# gwx-control.net
KiCad netlist of a schematic drawn in EAGLE
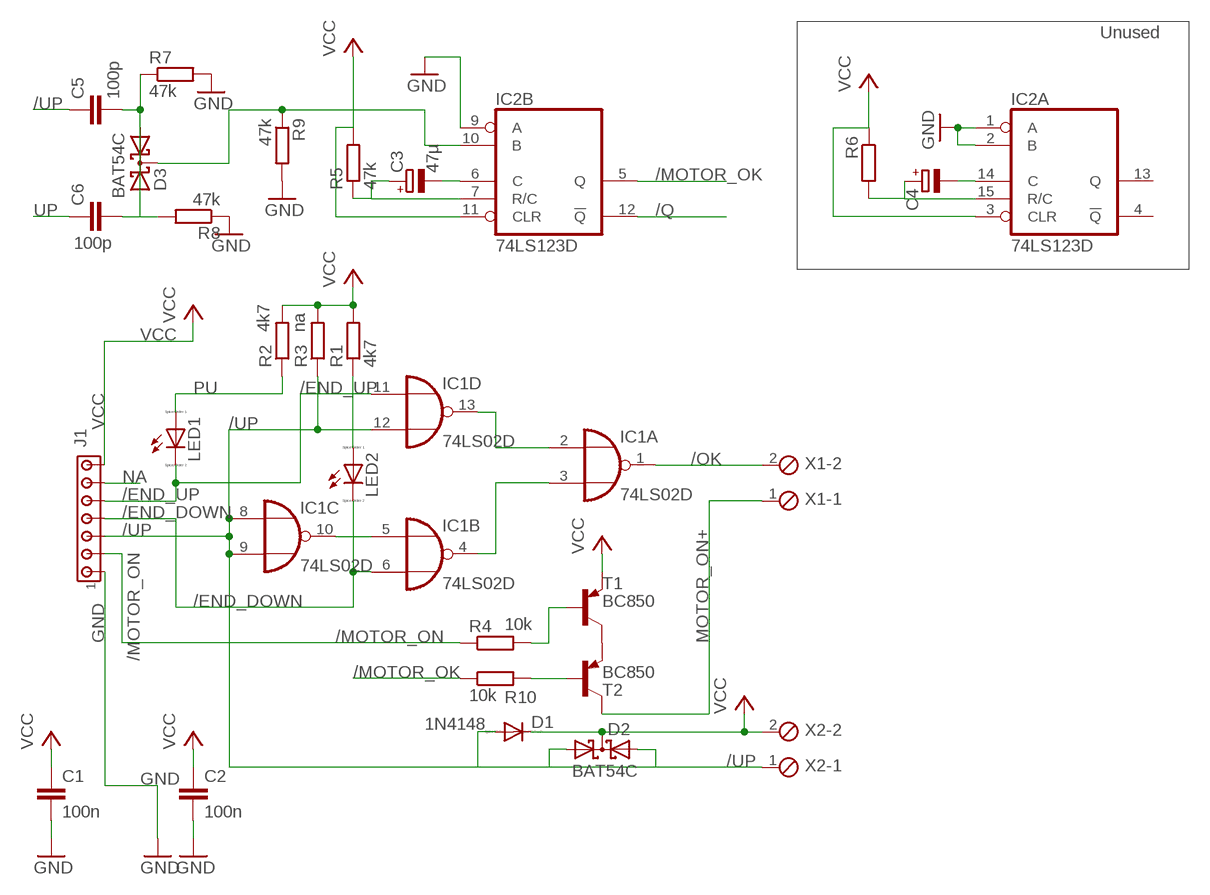
[diagram p0: schematic, sheet 1]

(export (version "E")
  (design (tool "Eeschema 10.0.6"))
  (components
    (comp (ref "C1")
      (value "100n")
      (footprint "eagle-import:C0603K")
      (libsource (lib "eagle-import") (part "C-EUC0603K"))
    )
    (comp (ref "C2")
      (value "100n")
      (footprint "eagle-import:C0603K")
      (libsource (lib "eagle-import") (part "C-EUC0603K"))
    )
    (comp (ref "C3")
      (value "47µ")
      (footprint "eagle-import:E5-6")
      (libsource (lib "eagle-import") (part "CPOL-EUE5-6"))
    )
    (comp (ref "C4")
      (value "CPOL-EUE5-6")
      (footprint "eagle-import:E5-6")
      (libsource (lib "eagle-import") (part "CPOL-EUE5-6"))
    )
    (comp (ref "C5")
      (value "100p")
      (footprint "eagle-import:C0603K")
      (libsource (lib "eagle-import") (part "C-EUC0603K"))
    )
    (comp (ref "C6")
      (value "100p")
      (footprint "eagle-import:C0603K")
      (libsource (lib "eagle-import") (part "C-EUC0603K"))
    )
    (comp (ref "D1")
      (value "1N4148")
      (footprint "eagle-import:DO35-10")
      (libsource (lib "eagle-import") (part "1N4148DO35-10"))
    )
    (comp (ref "D2")
      (value "BAT54C")
      (footprint "eagle-import:SOT23")
      (libsource (lib "eagle-import") (part "BAT54C"))
    )
    (comp (ref "D3")
      (value "BAT54C")
      (footprint "eagle-import:SOT23")
      (libsource (lib "eagle-import") (part "BAT54C"))
    )
    (comp (ref "IC1")
      (value "74LS02D")
      (footprint "eagle-import:SO14")
      (libsource (lib "eagle-import") (part "7402DLS"))
    )
    (comp (ref "IC2")
      (value "74LS123D")
      (footprint "eagle-import:SO16")
      (libsource (lib "eagle-import") (part "74123DLS"))
    )
    (comp (ref "J1")
      (value "MTA07-100")
      (footprint "eagle-import:10X07MTA")
      (libsource (lib "eagle-import") (part "MTA07-100"))
    )
    (comp (ref "LED1")
      (value "LED_ESML0603")
      (footprint "eagle-import:LED_SML0603")
      (libsource (lib "eagle-import") (part "LED_ESML0603"))
    )
    (comp (ref "LED2")
      (value "LED_ESML0603")
      (footprint "eagle-import:LED_SML0603")
      (libsource (lib "eagle-import") (part "LED_ESML0603"))
    )
    (comp (ref "R1")
      (value "4k7")
      (footprint "eagle-import:R0603")
      (libsource (lib "eagle-import") (part "resistor_R-EU_R0603"))
    )
    (comp (ref "R2")
      (value "4k7")
      (footprint "eagle-import:R0603")
      (libsource (lib "eagle-import") (part "resistor_R-EU_R0603"))
    )
    (comp (ref "R3")
      (value "na")
      (footprint "eagle-import:R0603")
      (libsource (lib "eagle-import") (part "resistor_R-EU_R0603"))
    )
    (comp (ref "R4")
      (value "10k")
      (footprint "eagle-import:R0603")
      (libsource (lib "eagle-import") (part "resistor_R-EU_R0603"))
    )
    (comp (ref "R5")
      (value "47k")
      (footprint "eagle-import:R0603")
      (libsource (lib "eagle-import") (part "R-EU_R0603"))
    )
    (comp (ref "R6")
      (value "R-EU_R0603")
      (footprint "eagle-import:R0603")
      (libsource (lib "eagle-import") (part "R-EU_R0603"))
    )
    (comp (ref "R7")
      (value "47k")
      (footprint "eagle-import:R0603")
      (libsource (lib "eagle-import") (part "R-EU_R0603"))
    )
    (comp (ref "R8")
      (value "47k")
      (footprint "eagle-import:R0603")
      (libsource (lib "eagle-import") (part "R-EU_R0603"))
    )
    (comp (ref "R9")
      (value "47k")
      (footprint "eagle-import:R0603")
      (libsource (lib "eagle-import") (part "R-EU_R0603"))
    )
    (comp (ref "R10")
      (value "10k")
      (footprint "eagle-import:R0603")
      (libsource (lib "eagle-import") (part "resistor_R-EU_R0603"))
    )
    (comp (ref "T1")
      (value "BC850")
      (footprint "eagle-import:SOT23-BEC")
      (libsource (lib "eagle-import") (part "-PNP-SOT23-BECBC856B"))
    )
    (comp (ref "T2")
      (value "BC850")
      (footprint "eagle-import:SOT23-BEC")
      (libsource (lib "eagle-import") (part "-PNP-SOT23-BECBC856B"))
    )
    (comp (ref "X1")
      (value "MPT2")
      (footprint "eagle-import:2POL254")
      (libsource (lib "eagle-import") (part "MPT2"))
    )
    (comp (ref "X2")
      (value "MPT2")
      (footprint "eagle-import:2POL254")
      (libsource (lib "eagle-import") (part "MPT2"))
    )
  )
  (nets
    (net (code "1") (name "/MOTOR_ON+") (class "Default")
      (node (ref "T2") (pin "C") (pinfunction "C_C") (pintype "passive"))
      (node (ref "X1") (pin "1") (pinfunction "1_1") (pintype "passive"))
    )
    (net (code "2") (name "/NA") (class "Default")
      (node (ref "J1") (pin "6") (pinfunction "6_6") (pintype "passive"))
    )
    (net (code "3") (name "/PU") (class "Default")
      (node (ref "LED1") (pin "A") (pinfunction "A_A") (pintype "passive"))
      (node (ref "R2") (pin "1") (pinfunction "1_1") (pintype "passive"))
    )
    (net (code "4") (name "/UP") (class "Default")
      (node (ref "C6") (pin "1") (pinfunction "1_1") (pintype "passive"))
      (node (ref "IC1") (pin "10") (pinfunction "O_10") (pintype "output"))
      (node (ref "IC1") (pin "5") (pinfunction "I0_5") (pintype "input"))
    )
    (net (code "5") (name "/{slash}END_DOWN") (class "Default")
      (node (ref "IC1") (pin "6") (pinfunction "I1_6") (pintype "input"))
      (node (ref "J1") (pin "4") (pinfunction "4_4") (pintype "passive"))
      (node (ref "LED2") (pin "C") (pinfunction "C_C") (pintype "passive"))
    )
    (net (code "6") (name "/{slash}END_UP") (class "Default")
      (node (ref "IC1") (pin "11") (pinfunction "I0_11") (pintype "input"))
      (node (ref "J1") (pin "5") (pinfunction "5_5") (pintype "passive"))
      (node (ref "LED1") (pin "C") (pinfunction "C_C") (pintype "passive"))
    )
    (net (code "7") (name "/{slash}MOTOR_OK") (class "Default")
      (node (ref "IC2") (pin "5") (pinfunction "Q_5") (pintype "output"))
      (node (ref "R10") (pin "1") (pinfunction "1_1") (pintype "passive"))
    )
    (net (code "8") (name "/{slash}MOTOR_ON") (class "Default")
      (node (ref "J1") (pin "2") (pinfunction "2_2") (pintype "passive"))
      (node (ref "R4") (pin "1") (pinfunction "1_1") (pintype "passive"))
    )
    (net (code "9") (name "/{slash}OK") (class "Default")
      (node (ref "IC1") (pin "1") (pinfunction "O_1") (pintype "output"))
      (node (ref "X1") (pin "2") (pinfunction "1_2") (pintype "passive"))
    )
    (net (code "10") (name "/{slash}Q") (class "Default")
      (node (ref "IC2") (pin "12") (pinfunction "~{Q}_12") (pintype "output"))
    )
    (net (code "11") (name "/{slash}UP") (class "Default")
      (node (ref "C5") (pin "1") (pinfunction "1_1") (pintype "passive"))
      (node (ref "D1") (pin "A") (pinfunction "A_A") (pintype "passive"))
      (node (ref "D2") (pin "1") (pinfunction "A1_1") (pintype "passive"))
      (node (ref "D2") (pin "2") (pinfunction "A2_2") (pintype "passive"))
      (node (ref "IC1") (pin "12") (pinfunction "I1_12") (pintype "input"))
      (node (ref "IC1") (pin "8") (pinfunction "I0_8") (pintype "input"))
      (node (ref "IC1") (pin "9") (pinfunction "I1_9") (pintype "input"))
      (node (ref "J1") (pin "3") (pinfunction "3_3") (pintype "passive"))
      (node (ref "R3") (pin "1") (pinfunction "1_1") (pintype "passive"))
      (node (ref "X2") (pin "1") (pinfunction "1_1") (pintype "passive"))
    )
    (net (code "12") (name "GND") (class "Default")
      (node (ref "C1") (pin "2") (pinfunction "2_2") (pintype "passive"))
      (node (ref "C2") (pin "2") (pinfunction "2_2") (pintype "passive"))
      (node (ref "IC2") (pin "1") (pinfunction "A_1") (pintype "input"))
      (node (ref "IC2") (pin "2") (pinfunction "B_2") (pintype "input"))
      (node (ref "IC2") (pin "9") (pinfunction "A_9") (pintype "input"))
      (node (ref "J1") (pin "1") (pinfunction "1_1") (pintype "passive"))
      (node (ref "R7") (pin "2") (pinfunction "2_2") (pintype "passive"))
      (node (ref "R8") (pin "1") (pinfunction "1_1") (pintype "passive"))
      (node (ref "R9") (pin "2") (pinfunction "2_2") (pintype "passive"))
    )
    (net (code "13") (name "Net-(D3-A1)") (class "Default")
      (node (ref "C6") (pin "2") (pinfunction "2_2") (pintype "passive"))
      (node (ref "D3") (pin "1") (pinfunction "A1_1") (pintype "passive"))
      (node (ref "R8") (pin "2") (pinfunction "2_2") (pintype "passive"))
    )
    (net (code "14") (name "Net-(D3-A2)") (class "Default")
      (node (ref "C5") (pin "2") (pinfunction "2_2") (pintype "passive"))
      (node (ref "D3") (pin "2") (pinfunction "A2_2") (pintype "passive"))
      (node (ref "R7") (pin "1") (pinfunction "1_1") (pintype "passive"))
    )
    (net (code "15") (name "Net-(D3-CC)") (class "Default")
      (node (ref "D3") (pin "3") (pinfunction "CC_3") (pintype "passive"))
      (node (ref "IC2") (pin "10") (pinfunction "B_10") (pintype "input"))
      (node (ref "R9") (pin "1") (pinfunction "1_1") (pintype "passive"))
    )
    (net (code "16") (name "Net-(IC1A-I0)") (class "Default")
      (node (ref "IC1") (pin "13") (pinfunction "O_13") (pintype "output"))
      (node (ref "IC1") (pin "2") (pinfunction "I0_2") (pintype "input"))
    )
    (net (code "17") (name "Net-(IC1A-I1)") (class "Default")
      (node (ref "IC1") (pin "3") (pinfunction "I1_3") (pintype "input"))
      (node (ref "IC1") (pin "4") (pinfunction "O_4") (pintype "output"))
    )
    (net (code "18") (name "Net-(IC2A-C)") (class "Default")
      (node (ref "C4") (pin "-") (pinfunction "-_-") (pintype "passive"))
      (node (ref "IC2") (pin "14") (pinfunction "C_14") (pintype "input"))
    )
    (net (code "19") (name "Net-(IC2A-R{slash}C)") (class "Default")
      (node (ref "C4") (pin "+") (pinfunction "+_+") (pintype "passive"))
      (node (ref "IC2") (pin "15") (pinfunction "R/C_15") (pintype "input"))
      (node (ref "R6") (pin "2") (pinfunction "2_2") (pintype "passive"))
    )
    (net (code "20") (name "Net-(IC2B-C)") (class "Default")
      (node (ref "C3") (pin "-") (pinfunction "-_-") (pintype "passive"))
      (node (ref "IC2") (pin "6") (pinfunction "C_6") (pintype "input"))
    )
    (net (code "21") (name "Net-(IC2B-R{slash}C)") (class "Default")
      (node (ref "C3") (pin "+") (pinfunction "+_+") (pintype "passive"))
      (node (ref "IC2") (pin "7") (pinfunction "R/C_7") (pintype "input"))
      (node (ref "R5") (pin "1") (pinfunction "1_1") (pintype "passive"))
    )
    (net (code "22") (name "Net-(LED2-PadA)") (class "Default")
      (node (ref "LED2") (pin "A") (pinfunction "A_A") (pintype "passive"))
      (node (ref "R1") (pin "1") (pinfunction "1_1") (pintype "passive"))
    )
    (net (code "23") (name "Net-(R4-Pad2)") (class "Default")
      (node (ref "R4") (pin "2") (pinfunction "2_2") (pintype "passive"))
      (node (ref "T1") (pin "B") (pinfunction "B_B") (pintype "passive"))
    )
    (net (code "24") (name "Net-(R10-Pad2)") (class "Default")
      (node (ref "R10") (pin "2") (pinfunction "2_2") (pintype "passive"))
      (node (ref "T2") (pin "B") (pinfunction "B_B") (pintype "passive"))
    )
    (net (code "25") (name "Net-(T1-PadC)") (class "Default")
      (node (ref "T1") (pin "C") (pinfunction "C_C") (pintype "passive"))
      (node (ref "T2") (pin "E") (pinfunction "E_E") (pintype "passive"))
    )
    (net (code "26") (name "VCC") (class "Default")
      (node (ref "C1") (pin "1") (pinfunction "1_1") (pintype "passive"))
      (node (ref "C2") (pin "1") (pinfunction "1_1") (pintype "passive"))
      (node (ref "D1") (pin "C") (pinfunction "C_C") (pintype "passive"))
      (node (ref "D2") (pin "3") (pinfunction "CC_3") (pintype "passive"))
      (node (ref "IC2") (pin "11") (pinfunction "CLR_11") (pintype "input"))
      (node (ref "IC2") (pin "3") (pinfunction "CLR_3") (pintype "input"))
      (node (ref "J1") (pin "7") (pinfunction "7_7") (pintype "passive"))
      (node (ref "R1") (pin "2") (pinfunction "2_2") (pintype "passive"))
      (node (ref "R2") (pin "2") (pinfunction "2_2") (pintype "passive"))
      (node (ref "R3") (pin "2") (pinfunction "2_2") (pintype "passive"))
      (node (ref "R5") (pin "2") (pinfunction "2_2") (pintype "passive"))
      (node (ref "R6") (pin "1") (pinfunction "1_1") (pintype "passive"))
      (node (ref "T1") (pin "E") (pinfunction "E_E") (pintype "passive"))
      (node (ref "X2") (pin "2") (pinfunction "1_2") (pintype "passive"))
    )
    (net (code "27") (name "unconnected-(IC2A-Q-Pad13)") (class "Default")
      (node (ref "IC2") (pin "13") (pinfunction "Q_13") (pintype "output"))
    )
    (net (code "28") (name "unconnected-(IC2A-~{Q}-Pad4)") (class "Default")
      (node (ref "IC2") (pin "4") (pinfunction "~{Q}_4") (pintype "output"))
    )
  )
)
